# HEAT.net
KiCad netlist of a schematic drawn in Altium Designer
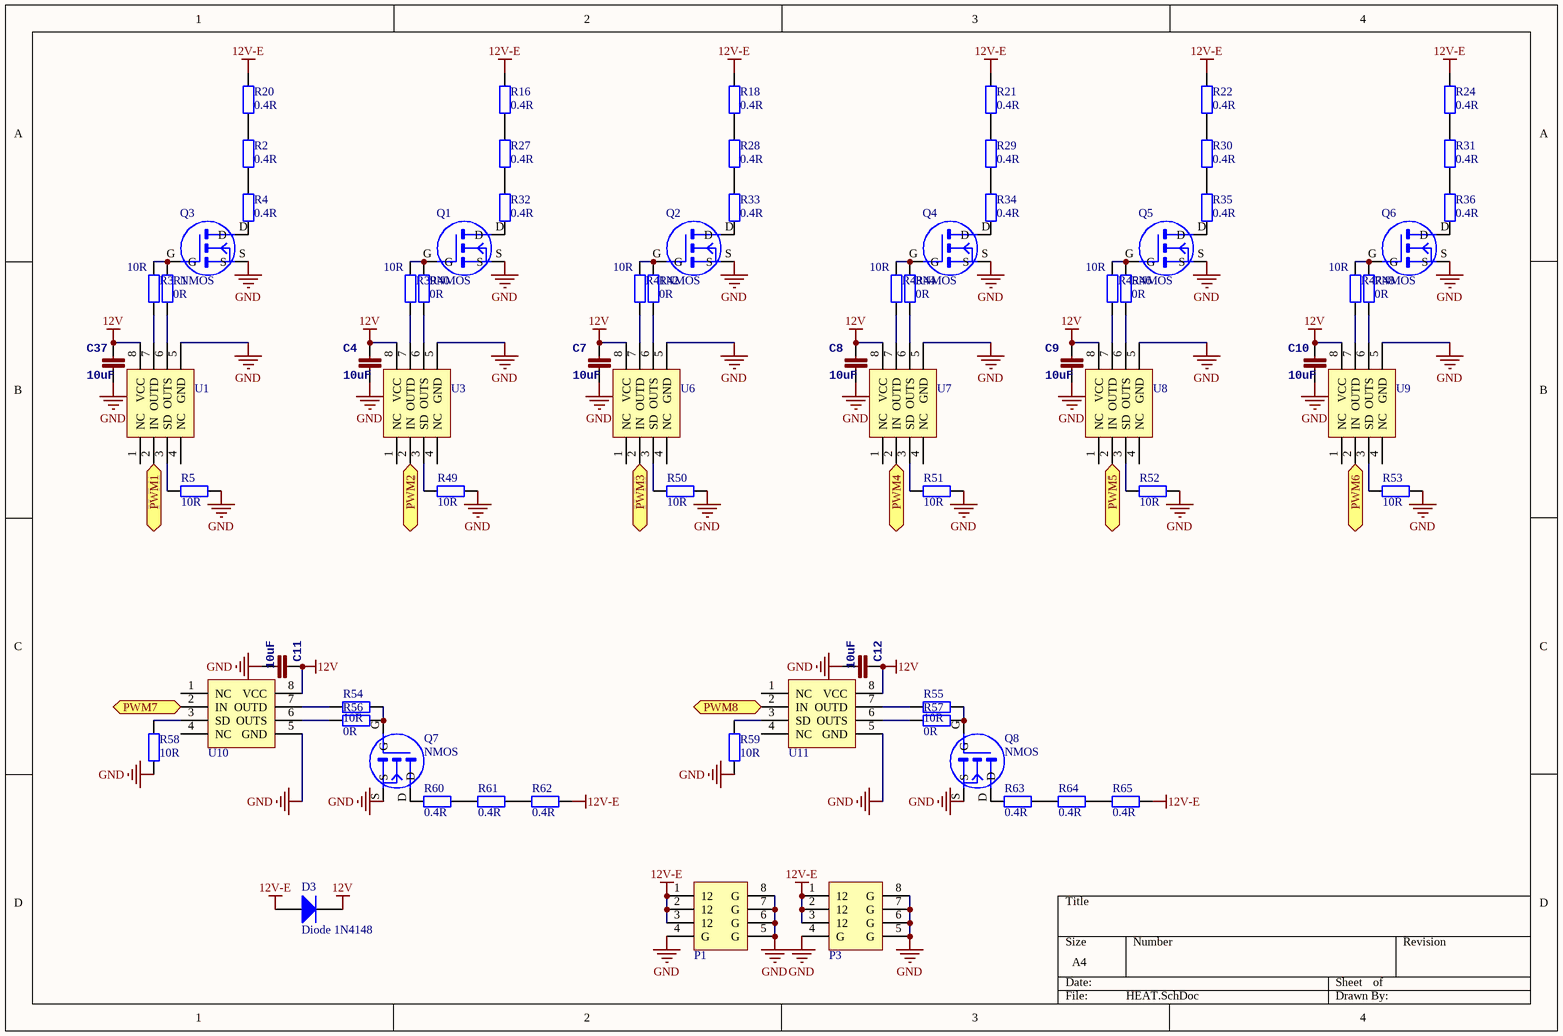
[diagram p0: HEAT.SchDoc]

(export (version "E")
  (design (tool "Eeschema 10.0.6"))
  (components
    (comp (ref "C4")
      (value "10uF")
      (footprint "0805")
      (description "<b>Capacitor</b>\nStandard 0603 ceramic capacitor, and 0.1\" leaded capacitor.")
      (fields (field (name "PARTNO") "CC0402ZRY5V7BB104"))
      (libsource (lib "pixhawk2") (part "CAP0402-CAP"))
    )
    (comp (ref "C7")
      (value "10uF")
      (footprint "0805")
      (description "<b>Capacitor</b>\nStandard 0603 ceramic capacitor, and 0.1\" leaded capacitor.")
      (fields (field (name "PARTNO") "CC0402ZRY5V7BB104"))
      (libsource (lib "pixhawk2") (part "CAP0402-CAP"))
    )
    (comp (ref "C8")
      (value "10uF")
      (footprint "0805")
      (description "<b>Capacitor</b>\nStandard 0603 ceramic capacitor, and 0.1\" leaded capacitor.")
      (fields (field (name "PARTNO") "CC0402ZRY5V7BB104"))
      (libsource (lib "pixhawk2") (part "CAP0402-CAP"))
    )
    (comp (ref "C9")
      (value "10uF")
      (footprint "0805")
      (description "<b>Capacitor</b>\nStandard 0603 ceramic capacitor, and 0.1\" leaded capacitor.")
      (fields (field (name "PARTNO") "CC0402ZRY5V7BB104"))
      (libsource (lib "pixhawk2") (part "CAP0402-CAP"))
    )
    (comp (ref "C10")
      (value "10uF")
      (footprint "0805")
      (description "<b>Capacitor</b>\nStandard 0603 ceramic capacitor, and 0.1\" leaded capacitor.")
      (fields (field (name "PARTNO") "CC0402ZRY5V7BB104"))
      (libsource (lib "pixhawk2") (part "CAP0402-CAP"))
    )
    (comp (ref "C11")
      (value "10uF")
      (footprint "0805")
      (description "<b>Capacitor</b>\nStandard 0603 ceramic capacitor, and 0.1\" leaded capacitor.")
      (fields (field (name "PARTNO") "CC0402ZRY5V7BB104"))
      (libsource (lib "") (part "CAP0402-CAP_1"))
    )
    (comp (ref "C12")
      (value "10uF")
      (footprint "0805")
      (description "<b>Capacitor</b>\nStandard 0603 ceramic capacitor, and 0.1\" leaded capacitor.")
      (fields (field (name "PARTNO") "CC0402ZRY5V7BB104"))
      (libsource (lib "") (part "CAP0402-CAP_1"))
    )
    (comp (ref "C37")
      (value "10uF")
      (footprint "0805")
      (description "<b>Capacitor</b>\nStandard 0603 ceramic capacitor, and 0.1\" leaded capacitor.")
      (fields (field (name "PARTNO") "CC0402ZRY5V7BB104"))
      (libsource (lib "pixhawk2") (part "CAP0402-CAP"))
    )
    (comp (ref "D3")
      (value "Diode 1N4148")
      (footprint "LC-SOD-323")
      (description "High Conductance Fast Diode")
      (fields (field (name "PUBLISHER") "Altium Limited"))
      (libsource (lib "Miscellaneous Devices") (part "Diode 1N4148"))
    )
    (comp (ref "P1") (value "PCIE-8P") (footprint "PCIE_8PIN") (libsource (lib "HEAT") (part "PCIE-8P")))
    (comp (ref "P3") (value "PCIE-8P") (footprint "PCIE_8PIN") (libsource (lib "HEAT") (part "PCIE-8P")))
    (comp (ref "Q1") (value "NMOS") (footprint "BSC025N03MS") (libsource (lib "PCB_Project") (part "NMOS")))
    (comp (ref "Q2") (value "NMOS") (footprint "BSC025N03MS") (libsource (lib "PCB_Project") (part "NMOS")))
    (comp (ref "Q3") (value "NMOS") (footprint "BSC025N03MS") (libsource (lib "PCB_Project") (part "NMOS")))
    (comp (ref "Q4") (value "NMOS") (footprint "BSC025N03MS") (libsource (lib "PCB_Project") (part "NMOS")))
    (comp (ref "Q5") (value "NMOS") (footprint "BSC025N03MS") (libsource (lib "PCB_Project") (part "NMOS")))
    (comp (ref "Q6") (value "NMOS") (footprint "BSC025N03MS") (libsource (lib "PCB_Project") (part "NMOS")))
    (comp (ref "Q7") (value "NMOS") (footprint "BSC025N03MS") (libsource (lib "PCB_Project") (part "NMOS")))
    (comp (ref "Q8") (value "NMOS") (footprint "BSC025N03MS") (libsource (lib "PCB_Project") (part "NMOS")))
    (comp (ref "R1")
      (value "0R")
      (footprint "0402")
      (description "Resistor")
      (fields (field (name "PUBLISHER") "Altium Limited"))
      (libsource (lib "") (part "Res2_1"))
    )
    (comp (ref "R2")
      (value "0.4R")
      (footprint "2512")
      (description "电阻")
      (fields (field (name "PUBLISHER") "Altium Limited"))
      (libsource (lib "mcu_board") (part "Res2"))
    )
    (comp (ref "R3")
      (value "10R")
      (footprint "0402")
      (description "Resistor")
      (fields (field (name "PUBLISHER") "Altium Limited"))
      (libsource (lib "") (part "Res2_1"))
    )
    (comp (ref "R4")
      (value "0.4R")
      (footprint "2512")
      (description "电阻")
      (fields (field (name "PUBLISHER") "Altium Limited"))
      (libsource (lib "mcu_board") (part "Res2"))
    )
    (comp (ref "R5")
      (value "10R")
      (footprint "0402")
      (description "Resistor")
      (fields (field (name "PUBLISHER") "Altium Limited"))
      (libsource (lib "Miscellaneous Devices") (part "Res2"))
    )
    (comp (ref "R16")
      (value "0.4R")
      (footprint "2512")
      (description "电阻")
      (fields (field (name "PUBLISHER") "Altium Limited"))
      (libsource (lib "mcu_board") (part "Res2"))
    )
    (comp (ref "R18")
      (value "0.4R")
      (footprint "2512")
      (description "电阻")
      (fields (field (name "PUBLISHER") "Altium Limited"))
      (libsource (lib "mcu_board") (part "Res2"))
    )
    (comp (ref "R20")
      (value "0.4R")
      (footprint "2512")
      (description "电阻")
      (fields (field (name "PUBLISHER") "Altium Limited"))
      (libsource (lib "mcu_board") (part "Res2"))
    )
    (comp (ref "R21")
      (value "0.4R")
      (footprint "2512")
      (description "电阻")
      (fields (field (name "PUBLISHER") "Altium Limited"))
      (libsource (lib "mcu_board") (part "Res2"))
    )
    (comp (ref "R22")
      (value "0.4R")
      (footprint "2512")
      (description "电阻")
      (fields (field (name "PUBLISHER") "Altium Limited"))
      (libsource (lib "mcu_board") (part "Res2"))
    )
    (comp (ref "R24")
      (value "0.4R")
      (footprint "2512")
      (description "电阻")
      (fields (field (name "PUBLISHER") "Altium Limited"))
      (libsource (lib "mcu_board") (part "Res2"))
    )
    (comp (ref "R27")
      (value "0.4R")
      (footprint "2512")
      (description "电阻")
      (fields (field (name "PUBLISHER") "Altium Limited"))
      (libsource (lib "mcu_board") (part "Res2"))
    )
    (comp (ref "R28")
      (value "0.4R")
      (footprint "2512")
      (description "电阻")
      (fields (field (name "PUBLISHER") "Altium Limited"))
      (libsource (lib "mcu_board") (part "Res2"))
    )
    (comp (ref "R29")
      (value "0.4R")
      (footprint "2512")
      (description "电阻")
      (fields (field (name "PUBLISHER") "Altium Limited"))
      (libsource (lib "mcu_board") (part "Res2"))
    )
    (comp (ref "R30")
      (value "0.4R")
      (footprint "2512")
      (description "电阻")
      (fields (field (name "PUBLISHER") "Altium Limited"))
      (libsource (lib "mcu_board") (part "Res2"))
    )
    (comp (ref "R31")
      (value "0.4R")
      (footprint "2512")
      (description "电阻")
      (fields (field (name "PUBLISHER") "Altium Limited"))
      (libsource (lib "mcu_board") (part "Res2"))
    )
    (comp (ref "R32")
      (value "0.4R")
      (footprint "2512")
      (description "电阻")
      (fields (field (name "PUBLISHER") "Altium Limited"))
      (libsource (lib "mcu_board") (part "Res2"))
    )
    (comp (ref "R33")
      (value "0.4R")
      (footprint "2512")
      (description "电阻")
      (fields (field (name "PUBLISHER") "Altium Limited"))
      (libsource (lib "mcu_board") (part "Res2"))
    )
    (comp (ref "R34")
      (value "0.4R")
      (footprint "2512")
      (description "电阻")
      (fields (field (name "PUBLISHER") "Altium Limited"))
      (libsource (lib "mcu_board") (part "Res2"))
    )
    (comp (ref "R35")
      (value "0.4R")
      (footprint "2512")
      (description "电阻")
      (fields (field (name "PUBLISHER") "Altium Limited"))
      (libsource (lib "mcu_board") (part "Res2"))
    )
    (comp (ref "R36")
      (value "0.4R")
      (footprint "2512")
      (description "电阻")
      (fields (field (name "PUBLISHER") "Altium Limited"))
      (libsource (lib "mcu_board") (part "Res2"))
    )
    (comp (ref "R39")
      (value "10R")
      (footprint "0402")
      (description "Resistor")
      (fields (field (name "PUBLISHER") "Altium Limited"))
      (libsource (lib "") (part "Res2_1"))
    )
    (comp (ref "R40")
      (value "0R")
      (footprint "0402")
      (description "Resistor")
      (fields (field (name "PUBLISHER") "Altium Limited"))
      (libsource (lib "") (part "Res2_1"))
    )
    (comp (ref "R41")
      (value "10R")
      (footprint "0402")
      (description "Resistor")
      (fields (field (name "PUBLISHER") "Altium Limited"))
      (libsource (lib "") (part "Res2_1"))
    )
    (comp (ref "R42")
      (value "0R")
      (footprint "0402")
      (description "Resistor")
      (fields (field (name "PUBLISHER") "Altium Limited"))
      (libsource (lib "") (part "Res2_1"))
    )
    (comp (ref "R43")
      (value "10R")
      (footprint "0402")
      (description "Resistor")
      (fields (field (name "PUBLISHER") "Altium Limited"))
      (libsource (lib "") (part "Res2_1"))
    )
    (comp (ref "R44")
      (value "0R")
      (footprint "0402")
      (description "Resistor")
      (fields (field (name "PUBLISHER") "Altium Limited"))
      (libsource (lib "") (part "Res2_1"))
    )
    (comp (ref "R45")
      (value "10R")
      (footprint "0402")
      (description "Resistor")
      (fields (field (name "PUBLISHER") "Altium Limited"))
      (libsource (lib "") (part "Res2_1"))
    )
    (comp (ref "R46")
      (value "0R")
      (footprint "0402")
      (description "Resistor")
      (fields (field (name "PUBLISHER") "Altium Limited"))
      (libsource (lib "") (part "Res2_1"))
    )
    (comp (ref "R47")
      (value "10R")
      (footprint "0402")
      (description "Resistor")
      (fields (field (name "PUBLISHER") "Altium Limited"))
      (libsource (lib "") (part "Res2_1"))
    )
    (comp (ref "R48")
      (value "0R")
      (footprint "0402")
      (description "Resistor")
      (fields (field (name "PUBLISHER") "Altium Limited"))
      (libsource (lib "") (part "Res2_1"))
    )
    (comp (ref "R49")
      (value "10R")
      (footprint "0402")
      (description "Resistor")
      (fields (field (name "PUBLISHER") "Altium Limited"))
      (libsource (lib "Miscellaneous Devices") (part "Res2"))
    )
    (comp (ref "R50")
      (value "10R")
      (footprint "0402")
      (description "Resistor")
      (fields (field (name "PUBLISHER") "Altium Limited"))
      (libsource (lib "Miscellaneous Devices") (part "Res2"))
    )
    (comp (ref "R51")
      (value "10R")
      (footprint "0402")
      (description "Resistor")
      (fields (field (name "PUBLISHER") "Altium Limited"))
      (libsource (lib "Miscellaneous Devices") (part "Res2"))
    )
    (comp (ref "R52")
      (value "10R")
      (footprint "0402")
      (description "Resistor")
      (fields (field (name "PUBLISHER") "Altium Limited"))
      (libsource (lib "Miscellaneous Devices") (part "Res2"))
    )
    (comp (ref "R53")
      (value "10R")
      (footprint "0402")
      (description "Resistor")
      (fields (field (name "PUBLISHER") "Altium Limited"))
      (libsource (lib "Miscellaneous Devices") (part "Res2"))
    )
    (comp (ref "R54")
      (value "10R")
      (footprint "0402")
      (description "Resistor")
      (fields (field (name "PUBLISHER") "Altium Limited"))
      (libsource (lib "") (part "Res2_2"))
    )
    (comp (ref "R55")
      (value "10R")
      (footprint "0402")
      (description "Resistor")
      (fields (field (name "PUBLISHER") "Altium Limited"))
      (libsource (lib "") (part "Res2_2"))
    )
    (comp (ref "R56")
      (value "0R")
      (footprint "0402")
      (description "Resistor")
      (fields (field (name "PUBLISHER") "Altium Limited"))
      (libsource (lib "") (part "Res2_2"))
    )
    (comp (ref "R57")
      (value "0R")
      (footprint "0402")
      (description "Resistor")
      (fields (field (name "PUBLISHER") "Altium Limited"))
      (libsource (lib "") (part "Res2_2"))
    )
    (comp (ref "R58")
      (value "10R")
      (footprint "0402")
      (description "Resistor")
      (fields (field (name "PUBLISHER") "Altium Limited"))
      (libsource (lib "") (part "Res2_1"))
    )
    (comp (ref "R59")
      (value "10R")
      (footprint "0402")
      (description "Resistor")
      (fields (field (name "PUBLISHER") "Altium Limited"))
      (libsource (lib "") (part "Res2_1"))
    )
    (comp (ref "R60")
      (value "0.4R")
      (footprint "2512")
      (description "电阻")
      (fields (field (name "PUBLISHER") "Altium Limited"))
      (libsource (lib "") (part "Res2_1"))
    )
    (comp (ref "R61")
      (value "0.4R")
      (footprint "2512")
      (description "电阻")
      (fields (field (name "PUBLISHER") "Altium Limited"))
      (libsource (lib "") (part "Res2_1"))
    )
    (comp (ref "R62")
      (value "0.4R")
      (footprint "2512")
      (description "电阻")
      (fields (field (name "PUBLISHER") "Altium Limited"))
      (libsource (lib "") (part "Res2_1"))
    )
    (comp (ref "R63")
      (value "0.4R")
      (footprint "2512")
      (description "电阻")
      (fields (field (name "PUBLISHER") "Altium Limited"))
      (libsource (lib "") (part "Res2_1"))
    )
    (comp (ref "R64")
      (value "0.4R")
      (footprint "2512")
      (description "电阻")
      (fields (field (name "PUBLISHER") "Altium Limited"))
      (libsource (lib "") (part "Res2_1"))
    )
    (comp (ref "R65")
      (value "0.4R")
      (footprint "2512")
      (description "电阻")
      (fields (field (name "PUBLISHER") "Altium Limited"))
      (libsource (lib "") (part "Res2_1"))
    )
    (comp (ref "U1") (value "EG2131") (footprint "SO8") (libsource (lib "HEAT") (part "EG2131")))
    (comp (ref "U3") (value "EG2131") (footprint "SO8") (libsource (lib "HEAT") (part "EG2131")))
    (comp (ref "U6") (value "EG2131") (footprint "SO8") (libsource (lib "HEAT") (part "EG2131")))
    (comp (ref "U7") (value "EG2131") (footprint "SO8") (libsource (lib "HEAT") (part "EG2131")))
    (comp (ref "U8") (value "EG2131") (footprint "SO8") (libsource (lib "HEAT") (part "EG2131")))
    (comp (ref "U9") (value "EG2131") (footprint "SO8") (libsource (lib "HEAT") (part "EG2131")))
    (comp (ref "U10") (value "EG2131") (footprint "SO8") (libsource (lib "") (part "EG2131_1")))
    (comp (ref "U11") (value "EG2131") (footprint "SO8") (libsource (lib "") (part "EG2131_1")))
  )
  (nets
    (net (code "1") (name "/PWM1") (class "Default")
      (node (ref "U1") (pin "2") (pinfunction "IN_2") (pintype "passive"))
    )
    (net (code "2") (name "/PWM2") (class "Default")
      (node (ref "U3") (pin "2") (pinfunction "IN_2") (pintype "passive"))
    )
    (net (code "3") (name "/PWM3") (class "Default")
      (node (ref "U6") (pin "2") (pinfunction "IN_2") (pintype "passive"))
    )
    (net (code "4") (name "/PWM4") (class "Default")
      (node (ref "U7") (pin "2") (pinfunction "IN_2") (pintype "passive"))
    )
    (net (code "5") (name "/PWM5") (class "Default")
      (node (ref "U8") (pin "2") (pinfunction "IN_2") (pintype "passive"))
    )
    (net (code "6") (name "/PWM6") (class "Default")
      (node (ref "U9") (pin "2") (pinfunction "IN_2") (pintype "passive"))
    )
    (net (code "7") (name "/PWM7") (class "Default")
      (node (ref "U10") (pin "2") (pinfunction "IN_2") (pintype "passive"))
    )
    (net (code "8") (name "/PWM8") (class "Default")
      (node (ref "U11") (pin "2") (pinfunction "IN_2") (pintype "passive"))
    )
    (net (code "9") (name "12V") (class "Default")
      (node (ref "C10") (pin "2") (pinfunction "2_2") (pintype "passive"))
      (node (ref "C11") (pin "2") (pinfunction "2_2") (pintype "passive"))
      (node (ref "C12") (pin "2") (pinfunction "2_2") (pintype "passive"))
      (node (ref "C37") (pin "2") (pinfunction "2_2") (pintype "passive"))
      (node (ref "C4") (pin "2") (pinfunction "2_2") (pintype "passive"))
      (node (ref "C7") (pin "2") (pinfunction "2_2") (pintype "passive"))
      (node (ref "C8") (pin "2") (pinfunction "2_2") (pintype "passive"))
      (node (ref "C9") (pin "2") (pinfunction "2_2") (pintype "passive"))
      (node (ref "D3") (pin "2") (pinfunction "K_2") (pintype "passive"))
      (node (ref "U1") (pin "8") (pinfunction "VCC_8") (pintype "passive"))
      (node (ref "U10") (pin "8") (pinfunction "VCC_8") (pintype "passive"))
      (node (ref "U11") (pin "8") (pinfunction "VCC_8") (pintype "passive"))
      (node (ref "U3") (pin "8") (pinfunction "VCC_8") (pintype "passive"))
      (node (ref "U6") (pin "8") (pinfunction "VCC_8") (pintype "passive"))
      (node (ref "U7") (pin "8") (pinfunction "VCC_8") (pintype "passive"))
      (node (ref "U8") (pin "8") (pinfunction "VCC_8") (pintype "passive"))
      (node (ref "U9") (pin "8") (pinfunction "VCC_8") (pintype "passive"))
    )
    (net (code "10") (name "12V-E") (class "Default")
      (node (ref "D3") (pin "1") (pinfunction "A_1") (pintype "passive"))
      (node (ref "P1") (pin "1") (pinfunction "12_1") (pintype "passive"))
      (node (ref "P1") (pin "2") (pinfunction "12_2") (pintype "passive"))
      (node (ref "P1") (pin "3") (pinfunction "12_3") (pintype "passive"))
      (node (ref "P3") (pin "1") (pinfunction "12_1") (pintype "passive"))
      (node (ref "P3") (pin "2") (pinfunction "12_2") (pintype "passive"))
      (node (ref "P3") (pin "3") (pinfunction "12_3") (pintype "passive"))
      (node (ref "R16") (pin "1") (pinfunction "1_1") (pintype "passive"))
      (node (ref "R18") (pin "1") (pinfunction "1_1") (pintype "passive"))
      (node (ref "R20") (pin "1") (pinfunction "1_1") (pintype "passive"))
      (node (ref "R21") (pin "1") (pinfunction "1_1") (pintype "passive"))
      (node (ref "R22") (pin "1") (pinfunction "1_1") (pintype "passive"))
      (node (ref "R24") (pin "1") (pinfunction "1_1") (pintype "passive"))
      (node (ref "R62") (pin "1") (pinfunction "1_1") (pintype "passive"))
      (node (ref "R65") (pin "1") (pinfunction "1_1") (pintype "passive"))
    )
    (net (code "11") (name "GND") (class "Default")
      (node (ref "C10") (pin "1") (pinfunction "1_1") (pintype "passive"))
      (node (ref "C11") (pin "1") (pinfunction "1_1") (pintype "passive"))
      (node (ref "C12") (pin "1") (pinfunction "1_1") (pintype "passive"))
      (node (ref "C37") (pin "1") (pinfunction "1_1") (pintype "passive"))
      (node (ref "C4") (pin "1") (pinfunction "1_1") (pintype "passive"))
      (node (ref "C7") (pin "1") (pinfunction "1_1") (pintype "passive"))
      (node (ref "C8") (pin "1") (pinfunction "1_1") (pintype "passive"))
      (node (ref "C9") (pin "1") (pinfunction "1_1") (pintype "passive"))
      (node (ref "P1") (pin "4") (pinfunction "G_4") (pintype "passive"))
      (node (ref "P1") (pin "5") (pinfunction "G_5") (pintype "passive"))
      (node (ref "P1") (pin "6") (pinfunction "G_6") (pintype "passive"))
      (node (ref "P1") (pin "7") (pinfunction "G_7") (pintype "passive"))
      (node (ref "P1") (pin "8") (pinfunction "G_8") (pintype "passive"))
      (node (ref "P3") (pin "4") (pinfunction "G_4") (pintype "passive"))
      (node (ref "P3") (pin "5") (pinfunction "G_5") (pintype "passive"))
      (node (ref "P3") (pin "6") (pinfunction "G_6") (pintype "passive"))
      (node (ref "P3") (pin "7") (pinfunction "G_7") (pintype "passive"))
      (node (ref "P3") (pin "8") (pinfunction "G_8") (pintype "passive"))
      (node (ref "Q1") (pin "S") (pinfunction "S_S") (pintype "passive"))
      (node (ref "Q2") (pin "S") (pinfunction "S_S") (pintype "passive"))
      (node (ref "Q3") (pin "S") (pinfunction "S_S") (pintype "passive"))
      (node (ref "Q4") (pin "S") (pinfunction "S_S") (pintype "passive"))
      (node (ref "Q5") (pin "S") (pinfunction "S_S") (pintype "passive"))
      (node (ref "Q6") (pin "S") (pinfunction "S_S") (pintype "passive"))
      (node (ref "Q7") (pin "S") (pinfunction "S_S") (pintype "passive"))
      (node (ref "Q8") (pin "S") (pinfunction "S_S") (pintype "passive"))
      (node (ref "R49") (pin "2") (pinfunction "2_2") (pintype "passive"))
      (node (ref "R5") (pin "2") (pinfunction "2_2") (pintype "passive"))
      (node (ref "R50") (pin "2") (pinfunction "2_2") (pintype "passive"))
      (node (ref "R51") (pin "2") (pinfunction "2_2") (pintype "passive"))
      (node (ref "R52") (pin "2") (pinfunction "2_2") (pintype "passive"))
      (node (ref "R53") (pin "2") (pinfunction "2_2") (pintype "passive"))
      (node (ref "R58") (pin "2") (pinfunction "2_2") (pintype "passive"))
      (node (ref "R59") (pin "2") (pinfunction "2_2") (pintype "passive"))
      (node (ref "U1") (pin "5") (pinfunction "GND_5") (pintype "passive"))
      (node (ref "U10") (pin "5") (pinfunction "GND_5") (pintype "passive"))
      (node (ref "U11") (pin "5") (pinfunction "GND_5") (pintype "passive"))
      (node (ref "U3") (pin "5") (pinfunction "GND_5") (pintype "passive"))
      (node (ref "U6") (pin "5") (pinfunction "GND_5") (pintype "passive"))
      (node (ref "U7") (pin "5") (pinfunction "GND_5") (pintype "passive"))
      (node (ref "U8") (pin "5") (pinfunction "GND_5") (pintype "passive"))
      (node (ref "U9") (pin "5") (pinfunction "GND_5") (pintype "passive"))
    )
    (net (code "12") (name "Net-(Q1-PadD)") (class "Default")
      (node (ref "Q1") (pin "D") (pinfunction "D_D") (pintype "passive"))
      (node (ref "R32") (pin "2") (pinfunction "2_2") (pintype "passive"))
    )
    (net (code "13") (name "Net-(Q1-PadG)") (class "Default")
      (node (ref "Q1") (pin "G") (pinfunction "G_G") (pintype "passive"))
      (node (ref "R39") (pin "1") (pinfunction "1_1") (pintype "passive"))
      (node (ref "R40") (pin "1") (pinfunction "1_1") (pintype "passive"))
    )
    (net (code "14") (name "Net-(Q2-PadD)") (class "Default")
      (node (ref "Q2") (pin "D") (pinfunction "D_D") (pintype "passive"))
      (node (ref "R33") (pin "2") (pinfunction "2_2") (pintype "passive"))
    )
    (net (code "15") (name "Net-(Q2-PadG)") (class "Default")
      (node (ref "Q2") (pin "G") (pinfunction "G_G") (pintype "passive"))
      (node (ref "R41") (pin "1") (pinfunction "1_1") (pintype "passive"))
      (node (ref "R42") (pin "1") (pinfunction "1_1") (pintype "passive"))
    )
    (net (code "16") (name "Net-(Q3-PadD)") (class "Default")
      (node (ref "Q3") (pin "D") (pinfunction "D_D") (pintype "passive"))
      (node (ref "R4") (pin "2") (pinfunction "2_2") (pintype "passive"))
    )
    (net (code "17") (name "Net-(Q3-PadG)") (class "Default")
      (node (ref "Q3") (pin "G") (pinfunction "G_G") (pintype "passive"))
      (node (ref "R1") (pin "1") (pinfunction "1_1") (pintype "passive"))
      (node (ref "R3") (pin "1") (pinfunction "1_1") (pintype "passive"))
    )
    (net (code "18") (name "Net-(Q4-PadD)") (class "Default")
      (node (ref "Q4") (pin "D") (pinfunction "D_D") (pintype "passive"))
      (node (ref "R34") (pin "2") (pinfunction "2_2") (pintype "passive"))
    )
    (net (code "19") (name "Net-(Q4-PadG)") (class "Default")
      (node (ref "Q4") (pin "G") (pinfunction "G_G") (pintype "passive"))
      (node (ref "R43") (pin "1") (pinfunction "1_1") (pintype "passive"))
      (node (ref "R44") (pin "1") (pinfunction "1_1") (pintype "passive"))
    )
    (net (code "20") (name "Net-(Q5-PadD)") (class "Default")
      (node (ref "Q5") (pin "D") (pinfunction "D_D") (pintype "passive"))
      (node (ref "R35") (pin "2") (pinfunction "2_2") (pintype "passive"))
    )
    (net (code "21") (name "Net-(Q5-PadG)") (class "Default")
      (node (ref "Q5") (pin "G") (pinfunction "G_G") (pintype "passive"))
      (node (ref "R45") (pin "1") (pinfunction "1_1") (pintype "passive"))
      (node (ref "R46") (pin "1") (pinfunction "1_1") (pintype "passive"))
    )
    (net (code "22") (name "Net-(Q6-PadD)") (class "Default")
      (node (ref "Q6") (pin "D") (pinfunction "D_D") (pintype "passive"))
      (node (ref "R36") (pin "2") (pinfunction "2_2") (pintype "passive"))
    )
    (net (code "23") (name "Net-(Q6-PadG)") (class "Default")
      (node (ref "Q6") (pin "G") (pinfunction "G_G") (pintype "passive"))
      (node (ref "R47") (pin "1") (pinfunction "1_1") (pintype "passive"))
      (node (ref "R48") (pin "1") (pinfunction "1_1") (pintype "passive"))
    )
    (net (code "24") (name "Net-(Q7-PadD)") (class "Default")
      (node (ref "Q7") (pin "D") (pinfunction "D_D") (pintype "passive"))
      (node (ref "R60") (pin "2") (pinfunction "2_2") (pintype "passive"))
    )
    (net (code "25") (name "Net-(Q7-PadG)") (class "Default")
      (node (ref "Q7") (pin "G") (pinfunction "G_G") (pintype "passive"))
      (node (ref "R54") (pin "1") (pinfunction "1_1") (pintype "passive"))
      (node (ref "R56") (pin "1") (pinfunction "1_1") (pintype "passive"))
    )
    (net (code "26") (name "Net-(Q8-PadD)") (class "Default")
      (node (ref "Q8") (pin "D") (pinfunction "D_D") (pintype "passive"))
      (node (ref "R63") (pin "2") (pinfunction "2_2") (pintype "passive"))
    )
    (net (code "27") (name "Net-(Q8-PadG)") (class "Default")
      (node (ref "Q8") (pin "G") (pinfunction "G_G") (pintype "passive"))
      (node (ref "R55") (pin "1") (pinfunction "1_1") (pintype "passive"))
      (node (ref "R57") (pin "1") (pinfunction "1_1") (pintype "passive"))
    )
    (net (code "28") (name "Net-(R2-Pad1)") (class "Default")
      (node (ref "R2") (pin "1") (pinfunction "1_1") (pintype "passive"))
      (node (ref "R20") (pin "2") (pinfunction "2_2") (pintype "passive"))
    )
    (net (code "29") (name "Net-(R2-Pad2)") (class "Default")
      (node (ref "R2") (pin "2") (pinfunction "2_2") (pintype "passive"))
      (node (ref "R4") (pin "1") (pinfunction "1_1") (pintype "passive"))
    )
    (net (code "30") (name "Net-(R16-Pad2)") (class "Default")
      (node (ref "R16") (pin "2") (pinfunction "2_2") (pintype "passive"))
      (node (ref "R27") (pin "1") (pinfunction "1_1") (pintype "passive"))
    )
    (net (code "31") (name "Net-(R18-Pad2)") (class "Default")
      (node (ref "R18") (pin "2") (pinfunction "2_2") (pintype "passive"))
      (node (ref "R28") (pin "1") (pinfunction "1_1") (pintype "passive"))
    )
    (net (code "32") (name "Net-(R21-Pad2)") (class "Default")
      (node (ref "R21") (pin "2") (pinfunction "2_2") (pintype "passive"))
      (node (ref "R29") (pin "1") (pinfunction "1_1") (pintype "passive"))
    )
    (net (code "33") (name "Net-(R22-Pad2)") (class "Default")
      (node (ref "R22") (pin "2") (pinfunction "2_2") (pintype "passive"))
      (node (ref "R30") (pin "1") (pinfunction "1_1") (pintype "passive"))
    )
    (net (code "34") (name "Net-(R24-Pad2)") (class "Default")
      (node (ref "R24") (pin "2") (pinfunction "2_2") (pintype "passive"))
      (node (ref "R31") (pin "1") (pinfunction "1_1") (pintype "passive"))
    )
    (net (code "35") (name "Net-(R27-Pad2)") (class "Default")
      (node (ref "R27") (pin "2") (pinfunction "2_2") (pintype "passive"))
      (node (ref "R32") (pin "1") (pinfunction "1_1") (pintype "passive"))
    )
    (net (code "36") (name "Net-(R28-Pad2)") (class "Default")
      (node (ref "R28") (pin "2") (pinfunction "2_2") (pintype "passive"))
      (node (ref "R33") (pin "1") (pinfunction "1_1") (pintype "passive"))
    )
    (net (code "37") (name "Net-(R29-Pad2)") (class "Default")
      (node (ref "R29") (pin "2") (pinfunction "2_2") (pintype "passive"))
      (node (ref "R34") (pin "1") (pinfunction "1_1") (pintype "passive"))
    )
    (net (code "38") (name "Net-(R30-Pad2)") (class "Default")
      (node (ref "R30") (pin "2") (pinfunction "2_2") (pintype "passive"))
      (node (ref "R35") (pin "1") (pinfunction "1_1") (pintype "passive"))
    )
    (net (code "39") (name "Net-(R31-Pad2)") (class "Default")
      (node (ref "R31") (pin "2") (pinfunction "2_2") (pintype "passive"))
      (node (ref "R36") (pin "1") (pinfunction "1_1") (pintype "passive"))
    )
    (net (code "40") (name "Net-(R60-Pad1)") (class "Default")
      (node (ref "R60") (pin "1") (pinfunction "1_1") (pintype "passive"))
      (node (ref "R61") (pin "2") (pinfunction "2_2") (pintype "passive"))
    )
    (net (code "41") (name "Net-(R61-Pad1)") (class "Default")
      (node (ref "R61") (pin "1") (pinfunction "1_1") (pintype "passive"))
      (node (ref "R62") (pin "2") (pinfunction "2_2") (pintype "passive"))
    )
    (net (code "42") (name "Net-(R63-Pad1)") (class "Default")
      (node (ref "R63") (pin "1") (pinfunction "1_1") (pintype "passive"))
      (node (ref "R64") (pin "2") (pinfunction "2_2") (pintype "passive"))
    )
    (net (code "43") (name "Net-(R64-Pad1)") (class "Default")
      (node (ref "R64") (pin "1") (pinfunction "1_1") (pintype "passive"))
      (node (ref "R65") (pin "2") (pinfunction "2_2") (pintype "passive"))
    )
    (net (code "44") (name "Net-(U1-OUTD)") (class "Default")
      (node (ref "R3") (pin "2") (pinfunction "2_2") (pintype "passive"))
      (node (ref "U1") (pin "7") (pinfunction "OUTD_7") (pintype "passive"))
    )
    (net (code "45") (name "Net-(U1-OUTS)") (class "Default")
      (node (ref "R1") (pin "2") (pinfunction "2_2") (pintype "passive"))
      (node (ref "U1") (pin "6") (pinfunction "OUTS_6") (pintype "passive"))
    )
    (net (code "46") (name "Net-(U1-SD)") (class "Default")
      (node (ref "R5") (pin "1") (pinfunction "1_1") (pintype "passive"))
      (node (ref "U1") (pin "3") (pinfunction "SD_3") (pintype "passive"))
    )
    (net (code "47") (name "Net-(U3-OUTD)") (class "Default")
      (node (ref "R39") (pin "2") (pinfunction "2_2") (pintype "passive"))
      (node (ref "U3") (pin "7") (pinfunction "OUTD_7") (pintype "passive"))
    )
    (net (code "48") (name "Net-(U3-OUTS)") (class "Default")
      (node (ref "R40") (pin "2") (pinfunction "2_2") (pintype "passive"))
      (node (ref "U3") (pin "6") (pinfunction "OUTS_6") (pintype "passive"))
    )
    (net (code "49") (name "Net-(U3-SD)") (class "Default")
      (node (ref "R49") (pin "1") (pinfunction "1_1") (pintype "passive"))
      (node (ref "U3") (pin "3") (pinfunction "SD_3") (pintype "passive"))
    )
    (net (code "50") (name "Net-(U6-OUTD)") (class "Default")
      (node (ref "R41") (pin "2") (pinfunction "2_2") (pintype "passive"))
      (node (ref "U6") (pin "7") (pinfunction "OUTD_7") (pintype "passive"))
    )
    (net (code "51") (name "Net-(U6-OUTS)") (class "Default")
      (node (ref "R42") (pin "2") (pinfunction "2_2") (pintype "passive"))
      (node (ref "U6") (pin "6") (pinfunction "OUTS_6") (pintype "passive"))
    )
    (net (code "52") (name "Net-(U6-SD)") (class "Default")
      (node (ref "R50") (pin "1") (pinfunction "1_1") (pintype "passive"))
      (node (ref "U6") (pin "3") (pinfunction "SD_3") (pintype "passive"))
    )
    (net (code "53") (name "Net-(U7-OUTD)") (class "Default")
      (node (ref "R43") (pin "2") (pinfunction "2_2") (pintype "passive"))
      (node (ref "U7") (pin "7") (pinfunction "OUTD_7") (pintype "passive"))
    )
    (net (code "54") (name "Net-(U7-OUTS)") (class "Default")
      (node (ref "R44") (pin "2") (pinfunction "2_2") (pintype "passive"))
      (node (ref "U7") (pin "6") (pinfunction "OUTS_6") (pintype "passive"))
    )
    (net (code "55") (name "Net-(U7-SD)") (class "Default")
      (node (ref "R51") (pin "1") (pinfunction "1_1") (pintype "passive"))
      (node (ref "U7") (pin "3") (pinfunction "SD_3") (pintype "passive"))
    )
    (net (code "56") (name "Net-(U8-OUTD)") (class "Default")
      (node (ref "R45") (pin "2") (pinfunction "2_2") (pintype "passive"))
      (node (ref "U8") (pin "7") (pinfunction "OUTD_7") (pintype "passive"))
    )
    (net (code "57") (name "Net-(U8-OUTS)") (class "Default")
      (node (ref "R46") (pin "2") (pinfunction "2_2") (pintype "passive"))
      (node (ref "U8") (pin "6") (pinfunction "OUTS_6") (pintype "passive"))
    )
    (net (code "58") (name "Net-(U8-SD)") (class "Default")
      (node (ref "R52") (pin "1") (pinfunction "1_1") (pintype "passive"))
      (node (ref "U8") (pin "3") (pinfunction "SD_3") (pintype "passive"))
    )
    (net (code "59") (name "Net-(U9-OUTD)") (class "Default")
      (node (ref "R47") (pin "2") (pinfunction "2_2") (pintype "passive"))
      (node (ref "U9") (pin "7") (pinfunction "OUTD_7") (pintype "passive"))
    )
    (net (code "60") (name "Net-(U9-OUTS)") (class "Default")
      (node (ref "R48") (pin "2") (pinfunction "2_2") (pintype "passive"))
      (node (ref "U9") (pin "6") (pinfunction "OUTS_6") (pintype "passive"))
    )
    (net (code "61") (name "Net-(U9-SD)") (class "Default")
      (node (ref "R53") (pin "1") (pinfunction "1_1") (pintype "passive"))
      (node (ref "U9") (pin "3") (pinfunction "SD_3") (pintype "passive"))
    )
    (net (code "62") (name "Net-(U10-OUTD)") (class "Default")
      (node (ref "R54") (pin "2") (pinfunction "2_2") (pintype "passive"))
      (node (ref "U10") (pin "7") (pinfunction "OUTD_7") (pintype "passive"))
    )
    (net (code "63") (name "Net-(U10-OUTS)") (class "Default")
      (node (ref "R56") (pin "2") (pinfunction "2_2") (pintype "passive"))
      (node (ref "U10") (pin "6") (pinfunction "OUTS_6") (pintype "passive"))
    )
    (net (code "64") (name "Net-(U10-SD)") (class "Default")
      (node (ref "R58") (pin "1") (pinfunction "1_1") (pintype "passive"))
      (node (ref "U10") (pin "3") (pinfunction "SD_3") (pintype "passive"))
    )
    (net (code "65") (name "Net-(U11-OUTD)") (class "Default")
      (node (ref "R55") (pin "2") (pinfunction "2_2") (pintype "passive"))
      (node (ref "U11") (pin "7") (pinfunction "OUTD_7") (pintype "passive"))
    )
    (net (code "66") (name "Net-(U11-OUTS)") (class "Default")
      (node (ref "R57") (pin "2") (pinfunction "2_2") (pintype "passive"))
      (node (ref "U11") (pin "6") (pinfunction "OUTS_6") (pintype "passive"))
    )
    (net (code "67") (name "Net-(U11-SD)") (class "Default")
      (node (ref "R59") (pin "1") (pinfunction "1_1") (pintype "passive"))
      (node (ref "U11") (pin "3") (pinfunction "SD_3") (pintype "passive"))
    )
    (net (code "68") (name "unconnected-(U1-NC-Pad1)") (class "Default")
      (node (ref "U1") (pin "1") (pinfunction "NC_1") (pintype "passive"))
    )
    (net (code "69") (name "unconnected-(U1-NC-Pad4)") (class "Default")
      (node (ref "U1") (pin "4") (pinfunction "NC_4") (pintype "passive"))
    )
    (net (code "70") (name "unconnected-(U3-NC-Pad1)") (class "Default")
      (node (ref "U3") (pin "1") (pinfunction "NC_1") (pintype "passive"))
    )
    (net (code "71") (name "unconnected-(U3-NC-Pad4)") (class "Default")
      (node (ref "U3") (pin "4") (pinfunction "NC_4") (pintype "passive"))
    )
    (net (code "72") (name "unconnected-(U6-NC-Pad1)") (class "Default")
      (node (ref "U6") (pin "1") (pinfunction "NC_1") (pintype "passive"))
    )
    (net (code "73") (name "unconnected-(U6-NC-Pad4)") (class "Default")
      (node (ref "U6") (pin "4") (pinfunction "NC_4") (pintype "passive"))
    )
    (net (code "74") (name "unconnected-(U7-NC-Pad1)") (class "Default")
      (node (ref "U7") (pin "1") (pinfunction "NC_1") (pintype "passive"))
    )
    (net (code "75") (name "unconnected-(U7-NC-Pad4)") (class "Default")
      (node (ref "U7") (pin "4") (pinfunction "NC_4") (pintype "passive"))
    )
    (net (code "76") (name "unconnected-(U8-NC-Pad1)") (class "Default")
      (node (ref "U8") (pin "1") (pinfunction "NC_1") (pintype "passive"))
    )
    (net (code "77") (name "unconnected-(U8-NC-Pad4)") (class "Default")
      (node (ref "U8") (pin "4") (pinfunction "NC_4") (pintype "passive"))
    )
    (net (code "78") (name "unconnected-(U9-NC-Pad1)") (class "Default")
      (node (ref "U9") (pin "1") (pinfunction "NC_1") (pintype "passive"))
    )
    (net (code "79") (name "unconnected-(U9-NC-Pad4)") (class "Default")
      (node (ref "U9") (pin "4") (pinfunction "NC_4") (pintype "passive"))
    )
    (net (code "80") (name "unconnected-(U10-NC-Pad1)") (class "Default")
      (node (ref "U10") (pin "1") (pinfunction "NC_1") (pintype "passive"))
    )
    (net (code "81") (name "unconnected-(U10-NC-Pad4)") (class "Default")
      (node (ref "U10") (pin "4") (pinfunction "NC_4") (pintype "passive"))
    )
    (net (code "82") (name "unconnected-(U11-NC-Pad1)") (class "Default")
      (node (ref "U11") (pin "1") (pinfunction "NC_1") (pintype "passive"))
    )
    (net (code "83") (name "unconnected-(U11-NC-Pad4)") (class "Default")
      (node (ref "U11") (pin "4") (pinfunction "NC_4") (pintype "passive"))
    )
  )
)
